# simple-loop-v3.net
KiCad netlist of a schematic drawn in EAGLE
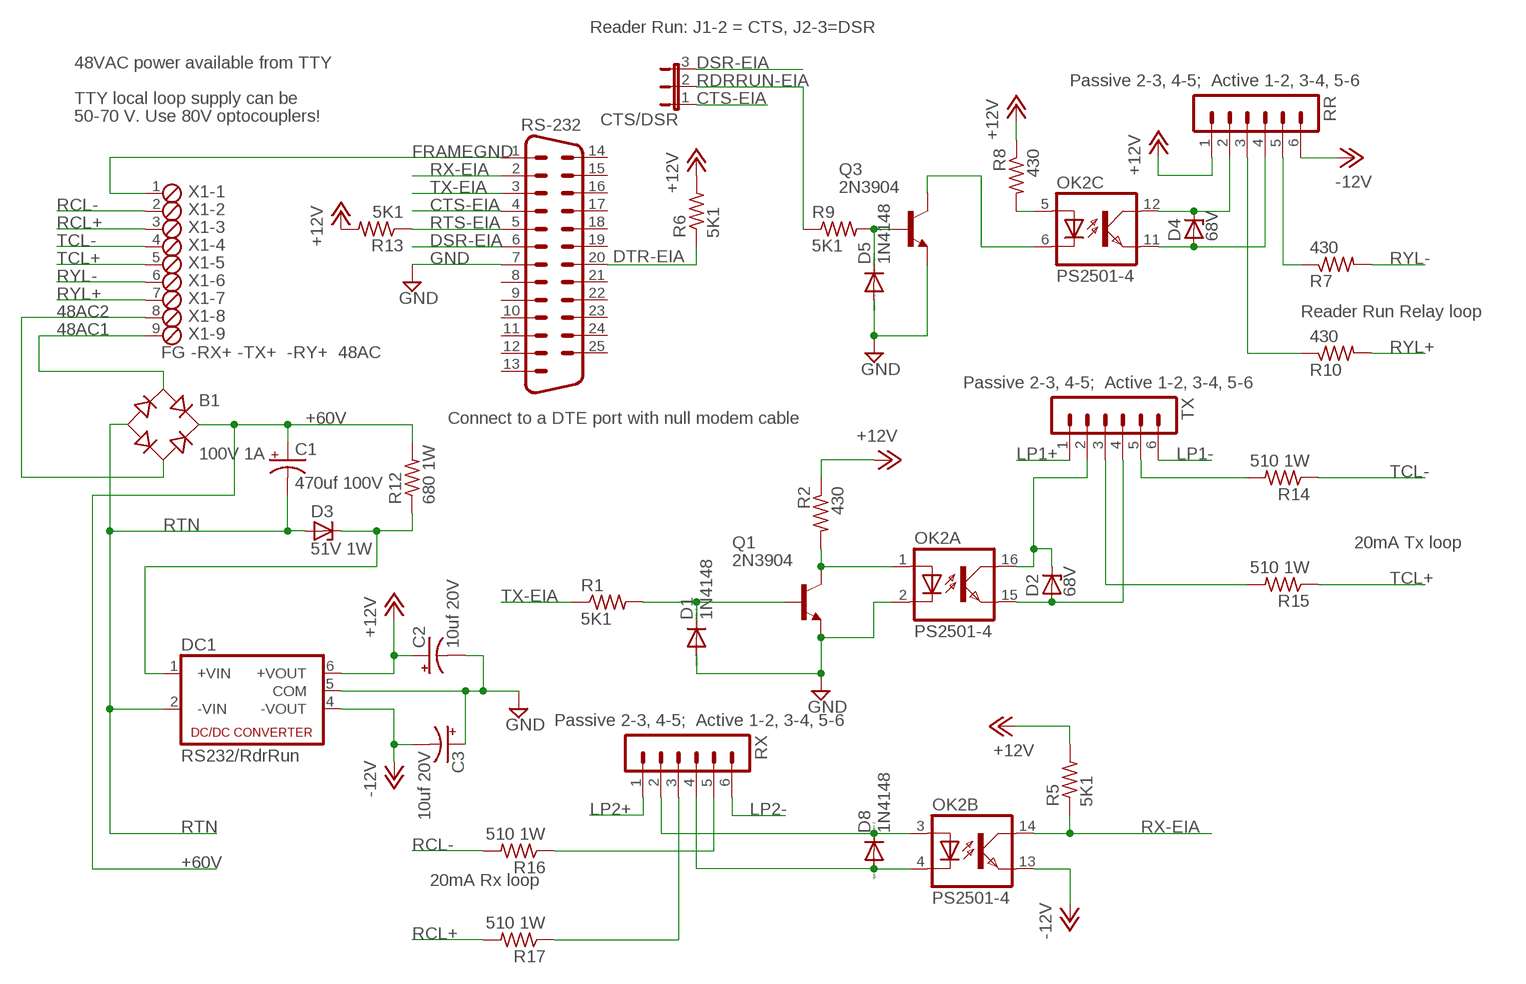
[diagram p0: schematic, sheet 1]
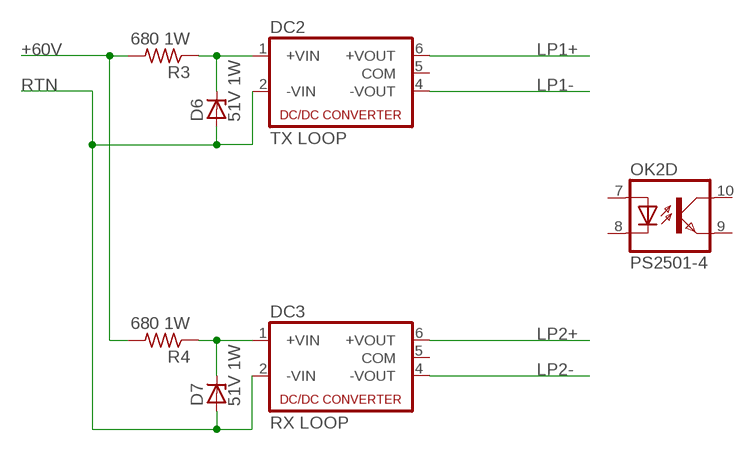
[diagram p1: schematic, sheet 2]

(export (version "E")
  (design (tool "Eeschema 10.0.6"))
  (components
    (comp (ref "B1")
      (value "100V 1A")
      (footprint "eagle-import:RB1A")
      (libsource (lib "eagle-import") (part "RB1A"))
    )
    (comp (ref "C1")
      (value "470uf 100V")
      (footprint "eagle-import:E7,5-18")
      (libsource (lib "eagle-import") (part "CPOL-USE7.5-18"))
    )
    (comp (ref "C2")
      (value "10uf 20V")
      (footprint "eagle-import:E2,5-6")
      (libsource (lib "eagle-import") (part "CPOL-USE2.5-6"))
    )
    (comp (ref "C3")
      (value "10uf 20V")
      (footprint "eagle-import:E2,5-6")
      (libsource (lib "eagle-import") (part "CPOL-USE2.5-6"))
    )
    (comp (ref "CTS/DSR")
      (value "JP2E")
      (footprint "eagle-import:JP2")
      (libsource (lib "eagle-import") (part "JP2E"))
    )
    (comp (ref "D1")
      (value "1N4148")
      (footprint "eagle-import:DO35-10")
      (libsource (lib "eagle-import") (part "1N4148DO35-10"))
    )
    (comp (ref "D2")
      (value "68V")
      (footprint "eagle-import:DO41Z10")
      (libsource (lib "eagle-import") (part "ZENER-DIODEDO41Z10"))
    )
    (comp (ref "D3")
      (value "51V 1W")
      (footprint "eagle-import:DO41Z10")
      (libsource (lib "eagle-import") (part "ZENER-DIODEDO41Z10"))
    )
    (comp (ref "D4")
      (value "68V")
      (footprint "eagle-import:DO41Z10")
      (libsource (lib "eagle-import") (part "ZENER-DIODEDO41Z10"))
    )
    (comp (ref "D5")
      (value "1N4148")
      (footprint "eagle-import:DO35-10")
      (libsource (lib "eagle-import") (part "1N4148DO35-10"))
    )
    (comp (ref "D8")
      (value "1N4148")
      (footprint "eagle-import:DO35-10")
      (libsource (lib "eagle-import") (part "1N4148DO35-10"))
    )
    (comp (ref "DC1")
      (value "RS232/RdrRun")
      (footprint "eagle-import:NMA")
      (fields (field (name "MF") "C & D TECHNOLOGIES, INC") (field (name "MPN") "NMA0515SC"))
      (libsource (lib "eagle-import") (part "NMA"))
    )
    (comp (ref "OK2")
      (value "PS2501-4")
      (footprint "eagle-import:DIL16")
      (libsource (lib "eagle-import") (part "PC847"))
    )
    (comp (ref "Q1")
      (value "2N3904")
      (footprint "eagle-import:TO92")
      (libsource (lib "eagle-import") (part "2N3904"))
    )
    (comp (ref "Q3")
      (value "2N3904")
      (footprint "eagle-import:TO92")
      (libsource (lib "eagle-import") (part "2N3904"))
    )
    (comp (ref "R1")
      (value "5K1")
      (footprint "eagle-import:0207_10")
      (libsource (lib "eagle-import") (part "R-US_0207/10"))
    )
    (comp (ref "R2")
      (value "430")
      (footprint "eagle-import:0207_10")
      (libsource (lib "eagle-import") (part "R-US_0207/10"))
    )
    (comp (ref "R5")
      (value "5K1")
      (footprint "eagle-import:0207_10")
      (libsource (lib "eagle-import") (part "R-US_0207/10"))
    )
    (comp (ref "R6")
      (value "5K1")
      (footprint "eagle-import:0207_10")
      (libsource (lib "eagle-import") (part "R-US_0207/10"))
    )
    (comp (ref "R7")
      (value "430")
      (footprint "eagle-import:0207_10")
      (libsource (lib "eagle-import") (part "R-US_0207/10"))
    )
    (comp (ref "R8")
      (value "430")
      (footprint "eagle-import:0207_10")
      (libsource (lib "eagle-import") (part "R-US_0207/10"))
    )
    (comp (ref "R9")
      (value "5K1")
      (footprint "eagle-import:0207_10")
      (libsource (lib "eagle-import") (part "R-US_0207/10"))
    )
    (comp (ref "R10")
      (value "430")
      (footprint "eagle-import:0207_10")
      (libsource (lib "eagle-import") (part "R-US_0207/10"))
    )
    (comp (ref "R12")
      (value "680 1W")
      (footprint "eagle-import:P0817V")
      (libsource (lib "eagle-import") (part "R-US_0817/7V"))
    )
    (comp (ref "R13")
      (value "5K1")
      (footprint "eagle-import:0207_10")
      (libsource (lib "eagle-import") (part "R-US_0207/10"))
    )
    (comp (ref "R14")
      (value "510 1W")
      (footprint "eagle-import:P0817V")
      (libsource (lib "eagle-import") (part "R-US_0817/7V"))
    )
    (comp (ref "R15")
      (value "510 1W")
      (footprint "eagle-import:P0817V")
      (libsource (lib "eagle-import") (part "R-US_0817/7V"))
    )
    (comp (ref "R16")
      (value "510 1W")
      (footprint "eagle-import:P0817V")
      (libsource (lib "eagle-import") (part "R-US_0817/7V"))
    )
    (comp (ref "R17")
      (value "510 1W")
      (footprint "eagle-import:P0817V")
      (libsource (lib "eagle-import") (part "R-US_0817/7V"))
    )
    (comp (ref "RR")
      (value "MA06-1")
      (footprint "eagle-import:MA06-1")
      (libsource (lib "eagle-import") (part "MA06-1"))
    )
    (comp (ref "RS-232")
      (value "M25H")
      (footprint "eagle-import:M25H")
      (libsource (lib "eagle-import") (part "M25H"))
    )
    (comp (ref "RX")
      (value "MA06-1")
      (footprint "eagle-import:MA06-1")
      (libsource (lib "eagle-import") (part "MA06-1"))
    )
    (comp (ref "TX")
      (value "MA06-1")
      (footprint "eagle-import:MA06-1")
      (libsource (lib "eagle-import") (part "MA06-1"))
    )
    (comp (ref "X1")
      (value "FG -RX+ -TX+ -RY+ 48AC")
      (footprint "eagle-import:9POL254")
      (libsource (lib "eagle-import") (part "MPT9"))
    )
    (comp (ref "D6")
      (value "51V 1W")
      (footprint "eagle-import:DO41Z10")
      (libsource (lib "eagle-import") (part "ZENER-DIODEDO41Z10"))
    )
    (comp (ref "D7")
      (value "51V 1W")
      (footprint "eagle-import:DO41Z10")
      (libsource (lib "eagle-import") (part "ZENER-DIODEDO41Z10"))
    )
    (comp (ref "DC2")
      (value "TX LOOP")
      (footprint "eagle-import:NMA")
      (fields (field (name "MF") "C & D TECHNOLOGIES, INC") (field (name "MPN") "NMA0515SC"))
      (libsource (lib "eagle-import") (part "NMA"))
    )
    (comp (ref "DC3")
      (value "RX LOOP")
      (footprint "eagle-import:NMA")
      (fields (field (name "MF") "C & D TECHNOLOGIES, INC") (field (name "MPN") "NMA0515SC"))
      (libsource (lib "eagle-import") (part "NMA"))
    )
    (comp (ref "R3")
      (value "680 1W")
      (footprint "eagle-import:P0817V")
      (libsource (lib "eagle-import") (part "R-US_0817/7V"))
    )
    (comp (ref "R4")
      (value "680 1W")
      (footprint "eagle-import:P0817V")
      (libsource (lib "eagle-import") (part "R-US_0817/7V"))
    )
  )
  (nets
    (net (code "1") (name "+12V") (class "Default")
      (node (ref "C2") (pin "+") (pinfunction "+_+") (pintype "passive"))
      (node (ref "DC1") (pin "6") (pinfunction "+VOUT_6") (pintype "passive"))
      (node (ref "R13") (pin "2") (pinfunction "2_2") (pintype "passive"))
      (node (ref "R2") (pin "1") (pinfunction "1_1") (pintype "passive"))
      (node (ref "R5") (pin "2") (pinfunction "2_2") (pintype "passive"))
      (node (ref "R6") (pin "2") (pinfunction "2_2") (pintype "passive"))
      (node (ref "R8") (pin "1") (pinfunction "1_1") (pintype "passive"))
      (node (ref "RR") (pin "1") (pinfunction "1_1") (pintype "passive"))
    )
    (net (code "2") (name "+60V") (class "Default")
      (node (ref "B1") (pin "+") (pinfunction "+_+") (pintype "passive"))
      (node (ref "C1") (pin "+") (pinfunction "+_+") (pintype "passive"))
      (node (ref "R12") (pin "2") (pinfunction "2_2") (pintype "passive"))
      (node (ref "R3") (pin "2") (pinfunction "2_2") (pintype "passive"))
      (node (ref "R4") (pin "2") (pinfunction "2_2") (pintype "passive"))
    )
    (net (code "3") (name "-12V") (class "Default")
      (node (ref "C3") (pin "-") (pinfunction "-_-") (pintype "passive"))
      (node (ref "DC1") (pin "4") (pinfunction "-VOUT_4") (pintype "passive"))
      (node (ref "OK2") (pin "13") (pinfunction "EMIT_13") (pintype "passive"))
      (node (ref "RR") (pin "6") (pinfunction "6_6") (pintype "passive"))
    )
    (net (code "4") (name "48AC1") (class "Default")
      (node (ref "B1") (pin "AC1") (pinfunction "AC1_AC1") (pintype "passive"))
      (node (ref "X1") (pin "9") (pinfunction "1_9") (pintype "passive"))
    )
    (net (code "5") (name "48AC2") (class "Default")
      (node (ref "B1") (pin "AC2") (pinfunction "AC2_AC2") (pintype "passive"))
      (node (ref "X1") (pin "8") (pinfunction "1_8") (pintype "passive"))
    )
    (net (code "6") (name "CTS-EIA") (class "Default")
      (node (ref "CTS/DSR") (pin "1") (pinfunction "1_1") (pintype "passive"))
      (node (ref "RS-232") (pin "4") (pinfunction "4_4") (pintype "passive"))
    )
    (net (code "7") (name "DSR-EIA") (class "Default")
      (node (ref "CTS/DSR") (pin "3") (pinfunction "3_3") (pintype "passive"))
      (node (ref "RS-232") (pin "6") (pinfunction "6_6") (pintype "passive"))
    )
    (net (code "8") (name "DTR-EIA") (class "Default")
      (node (ref "R6") (pin "1") (pinfunction "1_1") (pintype "passive"))
      (node (ref "RS-232") (pin "20") (pinfunction "20_20") (pintype "passive"))
    )
    (net (code "9") (name "FRAMEGND") (class "Default")
      (node (ref "RS-232") (pin "1") (pinfunction "1_1") (pintype "passive"))
      (node (ref "X1") (pin "1") (pinfunction "1_1") (pintype "passive"))
    )
    (net (code "10") (name "GND") (class "Default")
      (node (ref "C2") (pin "-") (pinfunction "-_-") (pintype "passive"))
      (node (ref "C3") (pin "+") (pinfunction "+_+") (pintype "passive"))
      (node (ref "D1") (pin "A") (pinfunction "A_A") (pintype "passive"))
      (node (ref "D5") (pin "A") (pinfunction "A_A") (pintype "passive"))
      (node (ref "DC1") (pin "5") (pinfunction "COM_5") (pintype "passive"))
      (node (ref "OK2") (pin "2") (pinfunction "C_2") (pintype "passive"))
      (node (ref "Q1") (pin "3") (pinfunction "E_3") (pintype "passive"))
      (node (ref "Q3") (pin "3") (pinfunction "E_3") (pintype "passive"))
      (node (ref "RS-232") (pin "7") (pinfunction "7_7") (pintype "passive"))
    )
    (net (code "11") (name "LP1+") (class "Default")
      (node (ref "DC2") (pin "6") (pinfunction "+VOUT_6") (pintype "passive"))
      (node (ref "TX") (pin "1") (pinfunction "1_1") (pintype "passive"))
    )
    (net (code "12") (name "LP1-") (class "Default")
      (node (ref "DC2") (pin "4") (pinfunction "-VOUT_4") (pintype "passive"))
      (node (ref "TX") (pin "6") (pinfunction "6_6") (pintype "passive"))
    )
    (net (code "13") (name "LP2+") (class "Default")
      (node (ref "DC3") (pin "6") (pinfunction "+VOUT_6") (pintype "passive"))
      (node (ref "RX") (pin "1") (pinfunction "1_1") (pintype "passive"))
    )
    (net (code "14") (name "LP2-") (class "Default")
      (node (ref "DC3") (pin "4") (pinfunction "-VOUT_4") (pintype "passive"))
      (node (ref "RX") (pin "6") (pinfunction "6_6") (pintype "passive"))
    )
    (net (code "15") (name "Net-(DC1-+VIN)") (class "Default")
      (node (ref "D3") (pin "C") (pinfunction "C_C") (pintype "passive"))
      (node (ref "DC1") (pin "1") (pinfunction "+VIN_1") (pintype "passive"))
      (node (ref "R12") (pin "1") (pinfunction "1_1") (pintype "passive"))
    )
    (net (code "16") (name "Net-(DC2-+VIN)") (class "Default")
      (node (ref "D6") (pin "C") (pinfunction "C_C") (pintype "passive"))
      (node (ref "DC2") (pin "1") (pinfunction "+VIN_1") (pintype "passive"))
      (node (ref "R3") (pin "1") (pinfunction "1_1") (pintype "passive"))
    )
    (net (code "17") (name "Net-(DC3-+VIN)") (class "Default")
      (node (ref "D7") (pin "C") (pinfunction "C_C") (pintype "passive"))
      (node (ref "DC3") (pin "1") (pinfunction "+VIN_1") (pintype "passive"))
      (node (ref "R4") (pin "1") (pinfunction "1_1") (pintype "passive"))
    )
    (net (code "18") (name "Net-(OK2A-A)") (class "Default")
      (node (ref "OK2") (pin "1") (pinfunction "A_1") (pintype "passive"))
      (node (ref "Q1") (pin "1") (pinfunction "C_1") (pintype "passive"))
      (node (ref "R2") (pin "2") (pinfunction "2_2") (pintype "passive"))
    )
    (net (code "19") (name "Net-(OK2A-COL)") (class "Default")
      (node (ref "D2") (pin "C") (pinfunction "C_C") (pintype "passive"))
      (node (ref "OK2") (pin "16") (pinfunction "COL_16") (pintype "passive"))
      (node (ref "TX") (pin "2") (pinfunction "2_2") (pintype "passive"))
    )
    (net (code "20") (name "Net-(OK2A-EMIT)") (class "Default")
      (node (ref "D2") (pin "A") (pinfunction "A_A") (pintype "passive"))
      (node (ref "OK2") (pin "15") (pinfunction "EMIT_15") (pintype "passive"))
      (node (ref "TX") (pin "4") (pinfunction "4_4") (pintype "passive"))
    )
    (net (code "21") (name "Net-(OK2B-A)") (class "Default")
      (node (ref "D8") (pin "C") (pinfunction "C_C") (pintype "passive"))
      (node (ref "OK2") (pin "3") (pinfunction "A_3") (pintype "passive"))
      (node (ref "RX") (pin "2") (pinfunction "2_2") (pintype "passive"))
    )
    (net (code "22") (name "Net-(OK2B-C)") (class "Default")
      (node (ref "D8") (pin "A") (pinfunction "A_A") (pintype "passive"))
      (node (ref "OK2") (pin "4") (pinfunction "C_4") (pintype "passive"))
      (node (ref "RX") (pin "4") (pinfunction "4_4") (pintype "passive"))
    )
    (net (code "23") (name "Net-(OK2C-A)") (class "Default")
      (node (ref "OK2") (pin "5") (pinfunction "A_5") (pintype "passive"))
      (node (ref "R8") (pin "2") (pinfunction "2_2") (pintype "passive"))
    )
    (net (code "24") (name "Net-(OK2C-C)") (class "Default")
      (node (ref "OK2") (pin "6") (pinfunction "C_6") (pintype "passive"))
      (node (ref "Q3") (pin "1") (pinfunction "C_1") (pintype "passive"))
    )
    (net (code "25") (name "Net-(OK2C-COL)") (class "Default")
      (node (ref "D4") (pin "C") (pinfunction "C_C") (pintype "passive"))
      (node (ref "OK2") (pin "12") (pinfunction "COL_12") (pintype "passive"))
      (node (ref "RR") (pin "2") (pinfunction "2_2") (pintype "passive"))
    )
    (net (code "26") (name "Net-(OK2C-EMIT)") (class "Default")
      (node (ref "D4") (pin "A") (pinfunction "A_A") (pintype "passive"))
      (node (ref "OK2") (pin "11") (pinfunction "EMIT_11") (pintype "passive"))
      (node (ref "RR") (pin "4") (pinfunction "4_4") (pintype "passive"))
    )
    (net (code "27") (name "Net-(Q1-B)") (class "Default")
      (node (ref "D1") (pin "C") (pinfunction "C_C") (pintype "passive"))
      (node (ref "Q1") (pin "2") (pinfunction "B_2") (pintype "passive"))
      (node (ref "R1") (pin "2") (pinfunction "2_2") (pintype "passive"))
    )
    (net (code "28") (name "Net-(Q3-B)") (class "Default")
      (node (ref "D5") (pin "C") (pinfunction "C_C") (pintype "passive"))
      (node (ref "Q3") (pin "2") (pinfunction "B_2") (pintype "passive"))
      (node (ref "R9") (pin "2") (pinfunction "2_2") (pintype "passive"))
    )
    (net (code "29") (name "Net-(R7-Pad1)") (class "Default")
      (node (ref "R7") (pin "1") (pinfunction "1_1") (pintype "passive"))
      (node (ref "RR") (pin "5") (pinfunction "5_5") (pintype "passive"))
    )
    (net (code "30") (name "Net-(R10-Pad1)") (class "Default")
      (node (ref "R10") (pin "1") (pinfunction "1_1") (pintype "passive"))
      (node (ref "RR") (pin "3") (pinfunction "3_3") (pintype "passive"))
    )
    (net (code "31") (name "Net-(R14-Pad2)") (class "Default")
      (node (ref "R14") (pin "2") (pinfunction "2_2") (pintype "passive"))
      (node (ref "TX") (pin "5") (pinfunction "5_5") (pintype "passive"))
    )
    (net (code "32") (name "Net-(R15-Pad2)") (class "Default")
      (node (ref "R15") (pin "2") (pinfunction "2_2") (pintype "passive"))
      (node (ref "TX") (pin "3") (pinfunction "3_3") (pintype "passive"))
    )
    (net (code "33") (name "Net-(R16-Pad1)") (class "Default")
      (node (ref "R16") (pin "1") (pinfunction "1_1") (pintype "passive"))
      (node (ref "RX") (pin "5") (pinfunction "5_5") (pintype "passive"))
    )
    (net (code "34") (name "Net-(R17-Pad1)") (class "Default")
      (node (ref "R17") (pin "1") (pinfunction "1_1") (pintype "passive"))
      (node (ref "RX") (pin "3") (pinfunction "3_3") (pintype "passive"))
    )
    (net (code "35") (name "RCL+") (class "Default")
      (node (ref "R17") (pin "2") (pinfunction "2_2") (pintype "passive"))
      (node (ref "X1") (pin "3") (pinfunction "1_3") (pintype "passive"))
    )
    (net (code "36") (name "RCL-") (class "Default")
      (node (ref "R16") (pin "2") (pinfunction "2_2") (pintype "passive"))
      (node (ref "X1") (pin "2") (pinfunction "1_2") (pintype "passive"))
    )
    (net (code "37") (name "RDRRUN-EIA") (class "Default")
      (node (ref "CTS/DSR") (pin "2") (pinfunction "2_2") (pintype "passive"))
      (node (ref "R9") (pin "1") (pinfunction "1_1") (pintype "passive"))
    )
    (net (code "38") (name "RTN") (class "Default")
      (node (ref "B1") (pin "-") (pinfunction "-_-") (pintype "passive"))
      (node (ref "C1") (pin "-") (pinfunction "-_-") (pintype "passive"))
      (node (ref "D3") (pin "A") (pinfunction "A_A") (pintype "passive"))
      (node (ref "D6") (pin "A") (pinfunction "A_A") (pintype "passive"))
      (node (ref "D7") (pin "A") (pinfunction "A_A") (pintype "passive"))
      (node (ref "DC1") (pin "2") (pinfunction "-VIN_2") (pintype "passive"))
      (node (ref "DC2") (pin "2") (pinfunction "-VIN_2") (pintype "passive"))
      (node (ref "DC3") (pin "2") (pinfunction "-VIN_2") (pintype "passive"))
    )
    (net (code "39") (name "RTS-EIA") (class "Default")
      (node (ref "R13") (pin "1") (pinfunction "1_1") (pintype "passive"))
      (node (ref "RS-232") (pin "5") (pinfunction "5_5") (pintype "passive"))
    )
    (net (code "40") (name "RX-EIA") (class "Default")
      (node (ref "OK2") (pin "14") (pinfunction "COL_14") (pintype "passive"))
      (node (ref "R5") (pin "1") (pinfunction "1_1") (pintype "passive"))
      (node (ref "RS-232") (pin "2") (pinfunction "2_2") (pintype "passive"))
    )
    (net (code "41") (name "RYL+") (class "Default")
      (node (ref "R10") (pin "2") (pinfunction "2_2") (pintype "passive"))
      (node (ref "X1") (pin "7") (pinfunction "1_7") (pintype "passive"))
    )
    (net (code "42") (name "RYL-") (class "Default")
      (node (ref "R7") (pin "2") (pinfunction "2_2") (pintype "passive"))
      (node (ref "X1") (pin "6") (pinfunction "1_6") (pintype "passive"))
    )
    (net (code "43") (name "TCL+") (class "Default")
      (node (ref "R15") (pin "1") (pinfunction "1_1") (pintype "passive"))
      (node (ref "X1") (pin "5") (pinfunction "1_5") (pintype "passive"))
    )
    (net (code "44") (name "TCL-") (class "Default")
      (node (ref "R14") (pin "1") (pinfunction "1_1") (pintype "passive"))
      (node (ref "X1") (pin "4") (pinfunction "1_4") (pintype "passive"))
    )
    (net (code "45") (name "TX-EIA") (class "Default")
      (node (ref "R1") (pin "1") (pinfunction "1_1") (pintype "passive"))
      (node (ref "RS-232") (pin "3") (pinfunction "3_3") (pintype "passive"))
    )
    (net (code "46") (name "unconnected-(DC2-COM-Pad5)") (class "Default")
      (node (ref "DC2") (pin "5") (pinfunction "COM_5") (pintype "passive"))
    )
    (net (code "47") (name "unconnected-(DC3-COM-Pad5)") (class "Default")
      (node (ref "DC3") (pin "5") (pinfunction "COM_5") (pintype "passive"))
    )
    (net (code "48") (name "unconnected-(OK2D-A-Pad7)") (class "Default")
      (node (ref "OK2") (pin "7") (pinfunction "A_7") (pintype "passive"))
    )
    (net (code "49") (name "unconnected-(OK2D-C-Pad8)") (class "Default")
      (node (ref "OK2") (pin "8") (pinfunction "C_8") (pintype "passive"))
    )
    (net (code "50") (name "unconnected-(OK2D-COL-Pad10)") (class "Default")
      (node (ref "OK2") (pin "10") (pinfunction "COL_10") (pintype "passive"))
    )
    (net (code "51") (name "unconnected-(OK2D-EMIT-Pad9)") (class "Default")
      (node (ref "OK2") (pin "9") (pinfunction "EMIT_9") (pintype "passive"))
    )
    (net (code "52") (name "unconnected-(RS-232-Pad8)") (class "Default")
      (node (ref "RS-232") (pin "8") (pinfunction "8_8") (pintype "passive"))
    )
    (net (code "53") (name "unconnected-(RS-232-Pad9)") (class "Default")
      (node (ref "RS-232") (pin "9") (pinfunction "9_9") (pintype "passive"))
    )
    (net (code "54") (name "unconnected-(RS-232-Pad10)") (class "Default")
      (node (ref "RS-232") (pin "10") (pinfunction "10_10") (pintype "passive"))
    )
    (net (code "55") (name "unconnected-(RS-232-Pad11)") (class "Default")
      (node (ref "RS-232") (pin "11") (pinfunction "11_11") (pintype "passive"))
    )
    (net (code "56") (name "unconnected-(RS-232-Pad12)") (class "Default")
      (node (ref "RS-232") (pin "12") (pinfunction "12_12") (pintype "passive"))
    )
    (net (code "57") (name "unconnected-(RS-232-Pad13)") (class "Default")
      (node (ref "RS-232") (pin "13") (pinfunction "13_13") (pintype "passive"))
    )
    (net (code "58") (name "unconnected-(RS-232-Pad14)") (class "Default")
      (node (ref "RS-232") (pin "14") (pinfunction "14_14") (pintype "passive"))
    )
    (net (code "59") (name "unconnected-(RS-232-Pad15)") (class "Default")
      (node (ref "RS-232") (pin "15") (pinfunction "15_15") (pintype "passive"))
    )
    (net (code "60") (name "unconnected-(RS-232-Pad16)") (class "Default")
      (node (ref "RS-232") (pin "16") (pinfunction "16_16") (pintype "passive"))
    )
    (net (code "61") (name "unconnected-(RS-232-Pad17)") (class "Default")
      (node (ref "RS-232") (pin "17") (pinfunction "17_17") (pintype "passive"))
    )
    (net (code "62") (name "unconnected-(RS-232-Pad18)") (class "Default")
      (node (ref "RS-232") (pin "18") (pinfunction "18_18") (pintype "passive"))
    )
    (net (code "63") (name "unconnected-(RS-232-Pad19)") (class "Default")
      (node (ref "RS-232") (pin "19") (pinfunction "19_19") (pintype "passive"))
    )
    (net (code "64") (name "unconnected-(RS-232-Pad21)") (class "Default")
      (node (ref "RS-232") (pin "21") (pinfunction "21_21") (pintype "passive"))
    )
    (net (code "65") (name "unconnected-(RS-232-Pad22)") (class "Default")
      (node (ref "RS-232") (pin "22") (pinfunction "22_22") (pintype "passive"))
    )
    (net (code "66") (name "unconnected-(RS-232-Pad23)") (class "Default")
      (node (ref "RS-232") (pin "23") (pinfunction "23_23") (pintype "passive"))
    )
    (net (code "67") (name "unconnected-(RS-232-Pad24)") (class "Default")
      (node (ref "RS-232") (pin "24") (pinfunction "24_24") (pintype "passive"))
    )
    (net (code "68") (name "unconnected-(RS-232-Pad25)") (class "Default")
      (node (ref "RS-232") (pin "25") (pinfunction "25_25") (pintype "passive"))
    )
  )
)
